# common_board_th.net
KiCad netlist of a schematic drawn in EAGLE
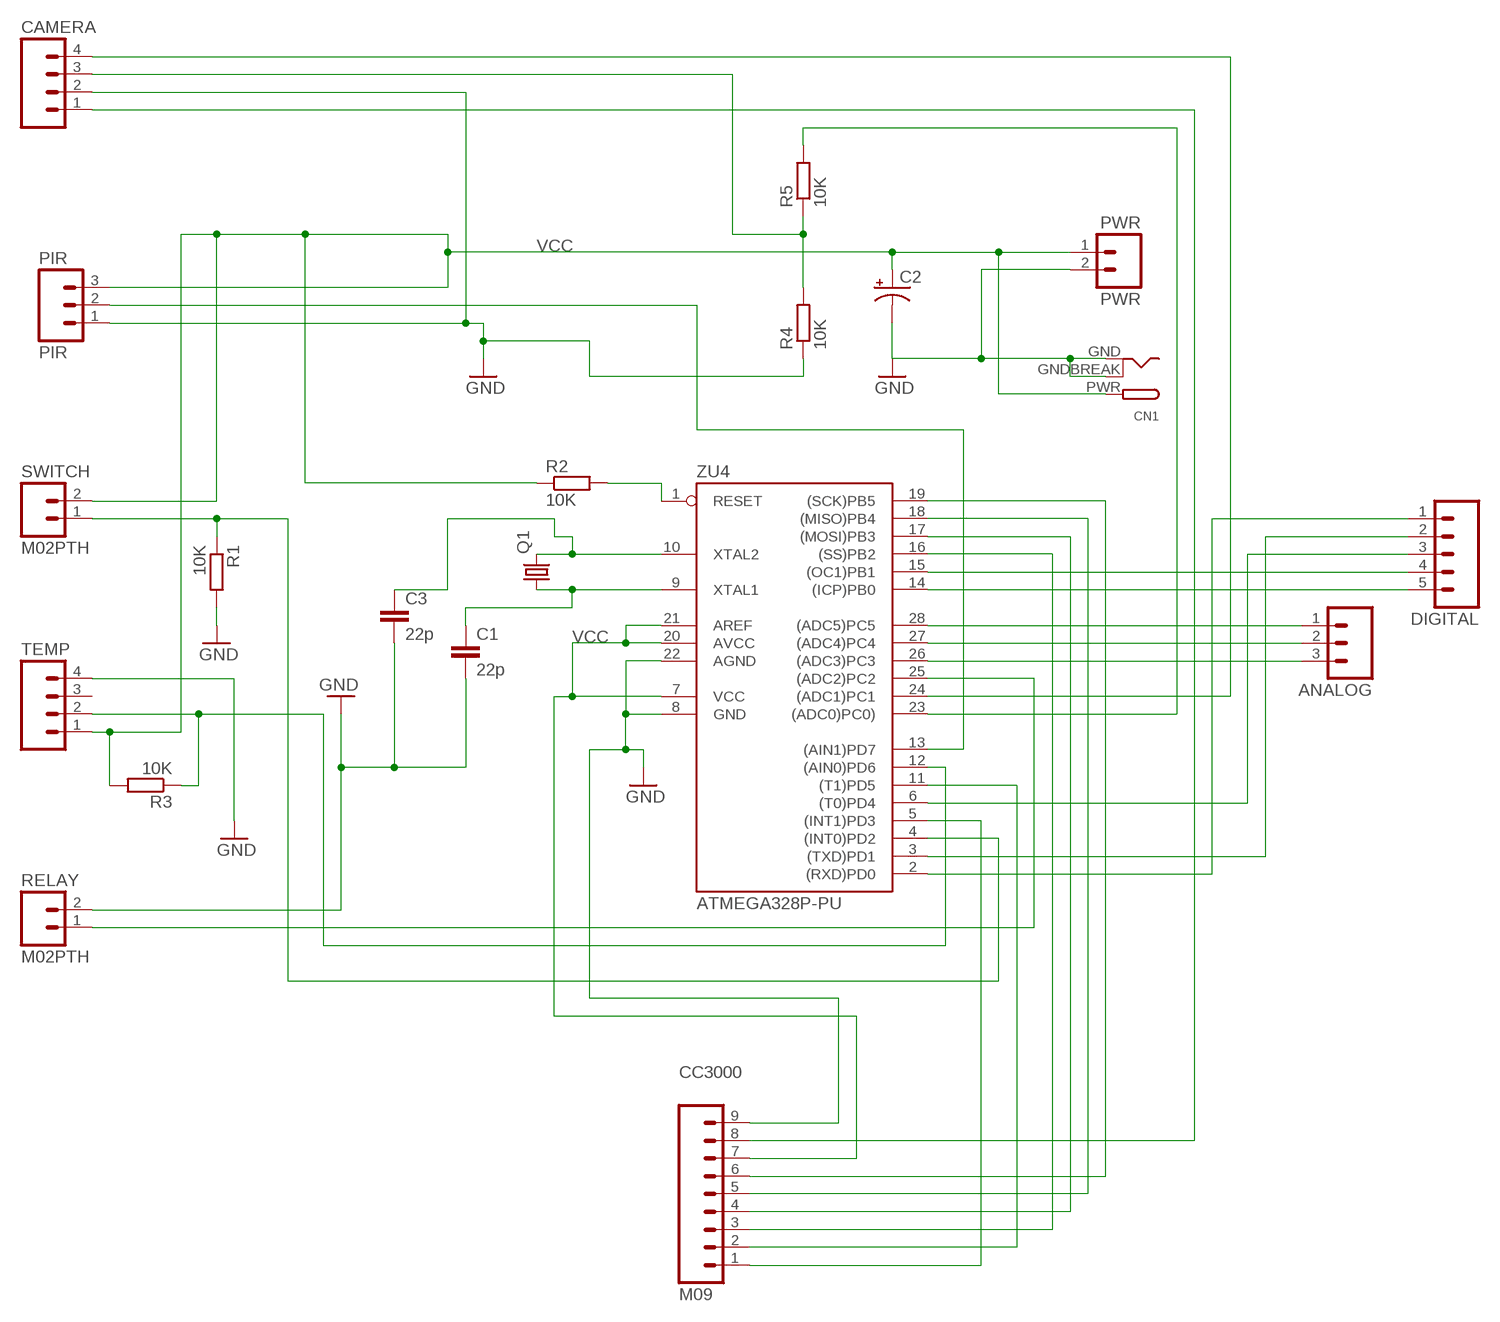
[diagram p0: schematic, sheet 1]

(export (version "E")
  (design (tool "Eeschema 10.0.6"))
  (components
    (comp (ref "ANALOG")
      (value "M03PTH")
      (footprint "eagle-import:1X03")
      (libsource (lib "eagle-import") (part "M03PTH"))
    )
    (comp (ref "C1")
      (value "22p")
      (footprint "eagle-import:C050-025X075")
      (libsource (lib "eagle-import") (part "C-EU050-025X075"))
    )
    (comp (ref "C2")
      (value "CAP_POLPTH1")
      (footprint "eagle-import:CPOL-RADIAL-100UF-25V")
      (libsource (lib "eagle-import") (part "CAP_POLPTH1"))
    )
    (comp (ref "C3")
      (value "22p")
      (footprint "eagle-import:C050-025X075")
      (libsource (lib "eagle-import") (part "C-EU050-025X075"))
    )
    (comp (ref "CAMERA")
      (value "M04PTH")
      (footprint "eagle-import:1X04")
      (libsource (lib "eagle-import") (part "M04PTH"))
    )
    (comp (ref "CC3000")
      (value "M09")
      (footprint "eagle-import:1X09")
      (libsource (lib "eagle-import") (part "M09"))
    )
    (comp (ref "CN1")
      (value "DCBARRELPTH")
      (footprint "eagle-import:DCJACK_2MM_PTH")
      (libsource (lib "eagle-import") (part "DCBARRELPTH"))
    )
    (comp (ref "DIGITAL")
      (value "M05PTH")
      (footprint "eagle-import:1X05")
      (libsource (lib "eagle-import") (part "M05PTH"))
    )
    (comp (ref "PIR")
      (value "PIR")
      (footprint "eagle-import:1X03")
      (libsource (lib "eagle-import") (part "M03PTH"))
    )
    (comp (ref "PWR")
      (value "PWR")
      (footprint "eagle-import:1X02")
      (libsource (lib "eagle-import") (part "M02PTH"))
    )
    (comp (ref "Q1")
      (value "CRYSTALHC49S")
      (footprint "eagle-import:HC49_S")
      (libsource (lib "eagle-import") (part "CRYSTALHC49S"))
    )
    (comp (ref "R1")
      (value "10K")
      (footprint "eagle-import:0207_7")
      (libsource (lib "eagle-import") (part "R-EU_0207/7"))
    )
    (comp (ref "R2")
      (value "10K")
      (footprint "eagle-import:0207_7")
      (libsource (lib "eagle-import") (part "R-EU_0207/7"))
    )
    (comp (ref "R3")
      (value "10K")
      (footprint "eagle-import:0207_7")
      (libsource (lib "eagle-import") (part "R-EU_0207/7"))
    )
    (comp (ref "R4")
      (value "10K")
      (footprint "eagle-import:0207_7")
      (libsource (lib "eagle-import") (part "R-EU_0207/7"))
    )
    (comp (ref "R5")
      (value "10K")
      (footprint "eagle-import:0207_7")
      (libsource (lib "eagle-import") (part "R-EU_0207/7"))
    )
    (comp (ref "RELAY")
      (value "M02PTH")
      (footprint "eagle-import:1X02")
      (libsource (lib "eagle-import") (part "M02PTH"))
    )
    (comp (ref "SWITCH")
      (value "M02PTH")
      (footprint "eagle-import:1X02")
      (libsource (lib "eagle-import") (part "M02PTH"))
    )
    (comp (ref "TEMP")
      (value "M04PTH")
      (footprint "eagle-import:1X04")
      (libsource (lib "eagle-import") (part "M04PTH"))
    )
    (comp (ref "ZU4")
      (value "ATMEGA328P-PU")
      (footprint "eagle-import:DIL28-3")
      (libsource (lib "eagle-import") (part "ATMEGA328P-PU"))
    )
  )
  (nets
    (net (code "1") (name "/VCC") (class "Default")
      (node (ref "C2") (pin "1") (pinfunction "+_1") (pintype "passive"))
      (node (ref "CC3000") (pin "7") (pinfunction "7_7") (pintype "passive"))
      (node (ref "CN1") (pin "PWR") (pinfunction "PWR_PWR") (pintype "power_in"))
      (node (ref "PIR") (pin "3") (pinfunction "3_3") (pintype "passive"))
      (node (ref "PWR") (pin "1") (pinfunction "1_1") (pintype "passive"))
      (node (ref "R2") (pin "1") (pinfunction "1_1") (pintype "passive"))
      (node (ref "R3") (pin "2") (pinfunction "2_2") (pintype "passive"))
      (node (ref "SWITCH") (pin "2") (pinfunction "2_2") (pintype "passive"))
      (node (ref "TEMP") (pin "1") (pinfunction "1_1") (pintype "passive"))
      (node (ref "ZU4") (pin "20") (pinfunction "AVCC_20") (pintype "power_in"))
      (node (ref "ZU4") (pin "21") (pinfunction "AREF_21") (pintype "passive"))
      (node (ref "ZU4") (pin "7") (pinfunction "VCC_7") (pintype "power_in"))
    )
    (net (code "2") (name "GND") (class "Default")
      (node (ref "C1") (pin "2") (pinfunction "2_2") (pintype "passive"))
      (node (ref "C2") (pin "2") (pinfunction "-_2") (pintype "passive"))
      (node (ref "C3") (pin "2") (pinfunction "2_2") (pintype "passive"))
      (node (ref "CAMERA") (pin "2") (pinfunction "2_2") (pintype "passive"))
      (node (ref "CC3000") (pin "9") (pinfunction "9_9") (pintype "passive"))
      (node (ref "CN1") (pin "GND") (pinfunction "GND_GND") (pintype "power_in"))
      (node (ref "CN1") (pin "GNDBREAK") (pinfunction "GNDBREAK_GNDBREAK") (pintype "power_in"))
      (node (ref "PIR") (pin "1") (pinfunction "1_1") (pintype "passive"))
      (node (ref "PWR") (pin "2") (pinfunction "2_2") (pintype "passive"))
      (node (ref "R1") (pin "2") (pinfunction "2_2") (pintype "passive"))
      (node (ref "R4") (pin "1") (pinfunction "1_1") (pintype "passive"))
      (node (ref "RELAY") (pin "2") (pinfunction "2_2") (pintype "passive"))
      (node (ref "TEMP") (pin "4") (pinfunction "4_4") (pintype "passive"))
      (node (ref "ZU4") (pin "22") (pinfunction "AGND_22") (pintype "power_in"))
      (node (ref "ZU4") (pin "8") (pinfunction "GND_8") (pintype "power_in"))
    )
    (net (code "3") (name "Net-(CAMERA-Pad1)") (class "Default")
      (node (ref "CAMERA") (pin "1") (pinfunction "1_1") (pintype "passive"))
      (node (ref "CC3000") (pin "8") (pinfunction "8_8") (pintype "passive"))
    )
    (net (code "4") (name "Net-(CAMERA-Pad3)") (class "Default")
      (node (ref "CAMERA") (pin "3") (pinfunction "3_3") (pintype "passive"))
      (node (ref "R4") (pin "2") (pinfunction "2_2") (pintype "passive"))
      (node (ref "R5") (pin "1") (pinfunction "1_1") (pintype "passive"))
    )
    (net (code "5") (name "Net-(ZU4-(ADC0)PC0))") (class "Default")
      (node (ref "R5") (pin "2") (pinfunction "2_2") (pintype "passive"))
      (node (ref "ZU4") (pin "23") (pinfunction "(ADC0)PC0)_23") (pintype "bidirectional"))
    )
    (net (code "6") (name "Net-(ZU4-(ADC1)PC1)") (class "Default")
      (node (ref "CAMERA") (pin "4") (pinfunction "4_4") (pintype "passive"))
      (node (ref "ZU4") (pin "24") (pinfunction "(ADC1)PC1_24") (pintype "bidirectional"))
    )
    (net (code "7") (name "Net-(ZU4-(ADC2)PC2)") (class "Default")
      (node (ref "RELAY") (pin "1") (pinfunction "1_1") (pintype "passive"))
      (node (ref "ZU4") (pin "25") (pinfunction "(ADC2)PC2_25") (pintype "bidirectional"))
    )
    (net (code "8") (name "Net-(ZU4-(ADC3)PC3)") (class "Default")
      (node (ref "ANALOG") (pin "3") (pinfunction "3_3") (pintype "passive"))
      (node (ref "ZU4") (pin "26") (pinfunction "(ADC3)PC3_26") (pintype "bidirectional"))
    )
    (net (code "9") (name "Net-(ZU4-(ADC4)PC4)") (class "Default")
      (node (ref "ANALOG") (pin "2") (pinfunction "2_2") (pintype "passive"))
      (node (ref "ZU4") (pin "27") (pinfunction "(ADC4)PC4_27") (pintype "bidirectional"))
    )
    (net (code "10") (name "Net-(ZU4-(ADC5)PC5)") (class "Default")
      (node (ref "ANALOG") (pin "1") (pinfunction "1_1") (pintype "passive"))
      (node (ref "ZU4") (pin "28") (pinfunction "(ADC5)PC5_28") (pintype "bidirectional"))
    )
    (net (code "11") (name "Net-(ZU4-(AIN0)PD6)") (class "Default")
      (node (ref "R3") (pin "1") (pinfunction "1_1") (pintype "passive"))
      (node (ref "TEMP") (pin "2") (pinfunction "2_2") (pintype "passive"))
      (node (ref "ZU4") (pin "12") (pinfunction "(AIN0)PD6_12") (pintype "bidirectional"))
    )
    (net (code "12") (name "Net-(ZU4-(AIN1)PD7)") (class "Default")
      (node (ref "PIR") (pin "2") (pinfunction "2_2") (pintype "passive"))
      (node (ref "ZU4") (pin "13") (pinfunction "(AIN1)PD7_13") (pintype "bidirectional"))
    )
    (net (code "13") (name "Net-(ZU4-(ICP)PB0)") (class "Default")
      (node (ref "DIGITAL") (pin "5") (pinfunction "5_5") (pintype "passive"))
      (node (ref "ZU4") (pin "14") (pinfunction "(ICP)PB0_14") (pintype "bidirectional"))
    )
    (net (code "14") (name "Net-(ZU4-(INT0)PD2)") (class "Default")
      (node (ref "R1") (pin "1") (pinfunction "1_1") (pintype "passive"))
      (node (ref "SWITCH") (pin "1") (pinfunction "1_1") (pintype "passive"))
      (node (ref "ZU4") (pin "4") (pinfunction "(INT0)PD2_4") (pintype "bidirectional"))
    )
    (net (code "15") (name "Net-(ZU4-(INT1)PD3)") (class "Default")
      (node (ref "CC3000") (pin "1") (pinfunction "1_1") (pintype "passive"))
      (node (ref "ZU4") (pin "5") (pinfunction "(INT1)PD3_5") (pintype "bidirectional"))
    )
    (net (code "16") (name "Net-(ZU4-(MISO)PB4)") (class "Default")
      (node (ref "CC3000") (pin "5") (pinfunction "5_5") (pintype "passive"))
      (node (ref "ZU4") (pin "18") (pinfunction "(MISO)PB4_18") (pintype "bidirectional"))
    )
    (net (code "17") (name "Net-(ZU4-(MOSI)PB3)") (class "Default")
      (node (ref "CC3000") (pin "4") (pinfunction "4_4") (pintype "passive"))
      (node (ref "ZU4") (pin "17") (pinfunction "(MOSI)PB3_17") (pintype "bidirectional"))
    )
    (net (code "18") (name "Net-(ZU4-(OC1)PB1)") (class "Default")
      (node (ref "DIGITAL") (pin "4") (pinfunction "4_4") (pintype "passive"))
      (node (ref "ZU4") (pin "15") (pinfunction "(OC1)PB1_15") (pintype "bidirectional"))
    )
    (net (code "19") (name "Net-(ZU4-(RXD)PD0)") (class "Default")
      (node (ref "DIGITAL") (pin "1") (pinfunction "1_1") (pintype "passive"))
      (node (ref "ZU4") (pin "2") (pinfunction "(RXD)PD0_2") (pintype "bidirectional"))
    )
    (net (code "20") (name "Net-(ZU4-(SCK)PB5)") (class "Default")
      (node (ref "CC3000") (pin "6") (pinfunction "6_6") (pintype "passive"))
      (node (ref "ZU4") (pin "19") (pinfunction "(SCK)PB5_19") (pintype "bidirectional"))
    )
    (net (code "21") (name "Net-(ZU4-(SS)PB2)") (class "Default")
      (node (ref "CC3000") (pin "3") (pinfunction "3_3") (pintype "passive"))
      (node (ref "ZU4") (pin "16") (pinfunction "(SS)PB2_16") (pintype "bidirectional"))
    )
    (net (code "22") (name "Net-(ZU4-(T0)PD4)") (class "Default")
      (node (ref "DIGITAL") (pin "3") (pinfunction "3_3") (pintype "passive"))
      (node (ref "ZU4") (pin "6") (pinfunction "(T0)PD4_6") (pintype "bidirectional"))
    )
    (net (code "23") (name "Net-(ZU4-(T1)PD5)") (class "Default")
      (node (ref "CC3000") (pin "2") (pinfunction "2_2") (pintype "passive"))
      (node (ref "ZU4") (pin "11") (pinfunction "(T1)PD5_11") (pintype "bidirectional"))
    )
    (net (code "24") (name "Net-(ZU4-(TXD)PD1)") (class "Default")
      (node (ref "DIGITAL") (pin "2") (pinfunction "2_2") (pintype "passive"))
      (node (ref "ZU4") (pin "3") (pinfunction "(TXD)PD1_3") (pintype "bidirectional"))
    )
    (net (code "25") (name "Net-(ZU4-RESET)") (class "Default")
      (node (ref "R2") (pin "2") (pinfunction "2_2") (pintype "passive"))
      (node (ref "ZU4") (pin "1") (pinfunction "RESET_1") (pintype "input"))
    )
    (net (code "26") (name "Net-(ZU4-XTAL1)") (class "Default")
      (node (ref "C1") (pin "1") (pinfunction "1_1") (pintype "passive"))
      (node (ref "Q1") (pin "1") (pinfunction "1_1") (pintype "passive"))
      (node (ref "ZU4") (pin "9") (pinfunction "XTAL1_9") (pintype "bidirectional"))
    )
    (net (code "27") (name "Net-(ZU4-XTAL2)") (class "Default")
      (node (ref "C3") (pin "1") (pinfunction "1_1") (pintype "passive"))
      (node (ref "Q1") (pin "2") (pinfunction "2_2") (pintype "passive"))
      (node (ref "ZU4") (pin "10") (pinfunction "XTAL2_10") (pintype "bidirectional"))
    )
    (net (code "28") (name "unconnected-(TEMP-Pad3)") (class "Default")
      (node (ref "TEMP") (pin "3") (pinfunction "3_3") (pintype "passive"))
    )
  )
)
